# Wind_Tree_connect.net
KiCad netlist of a schematic drawn in EAGLE
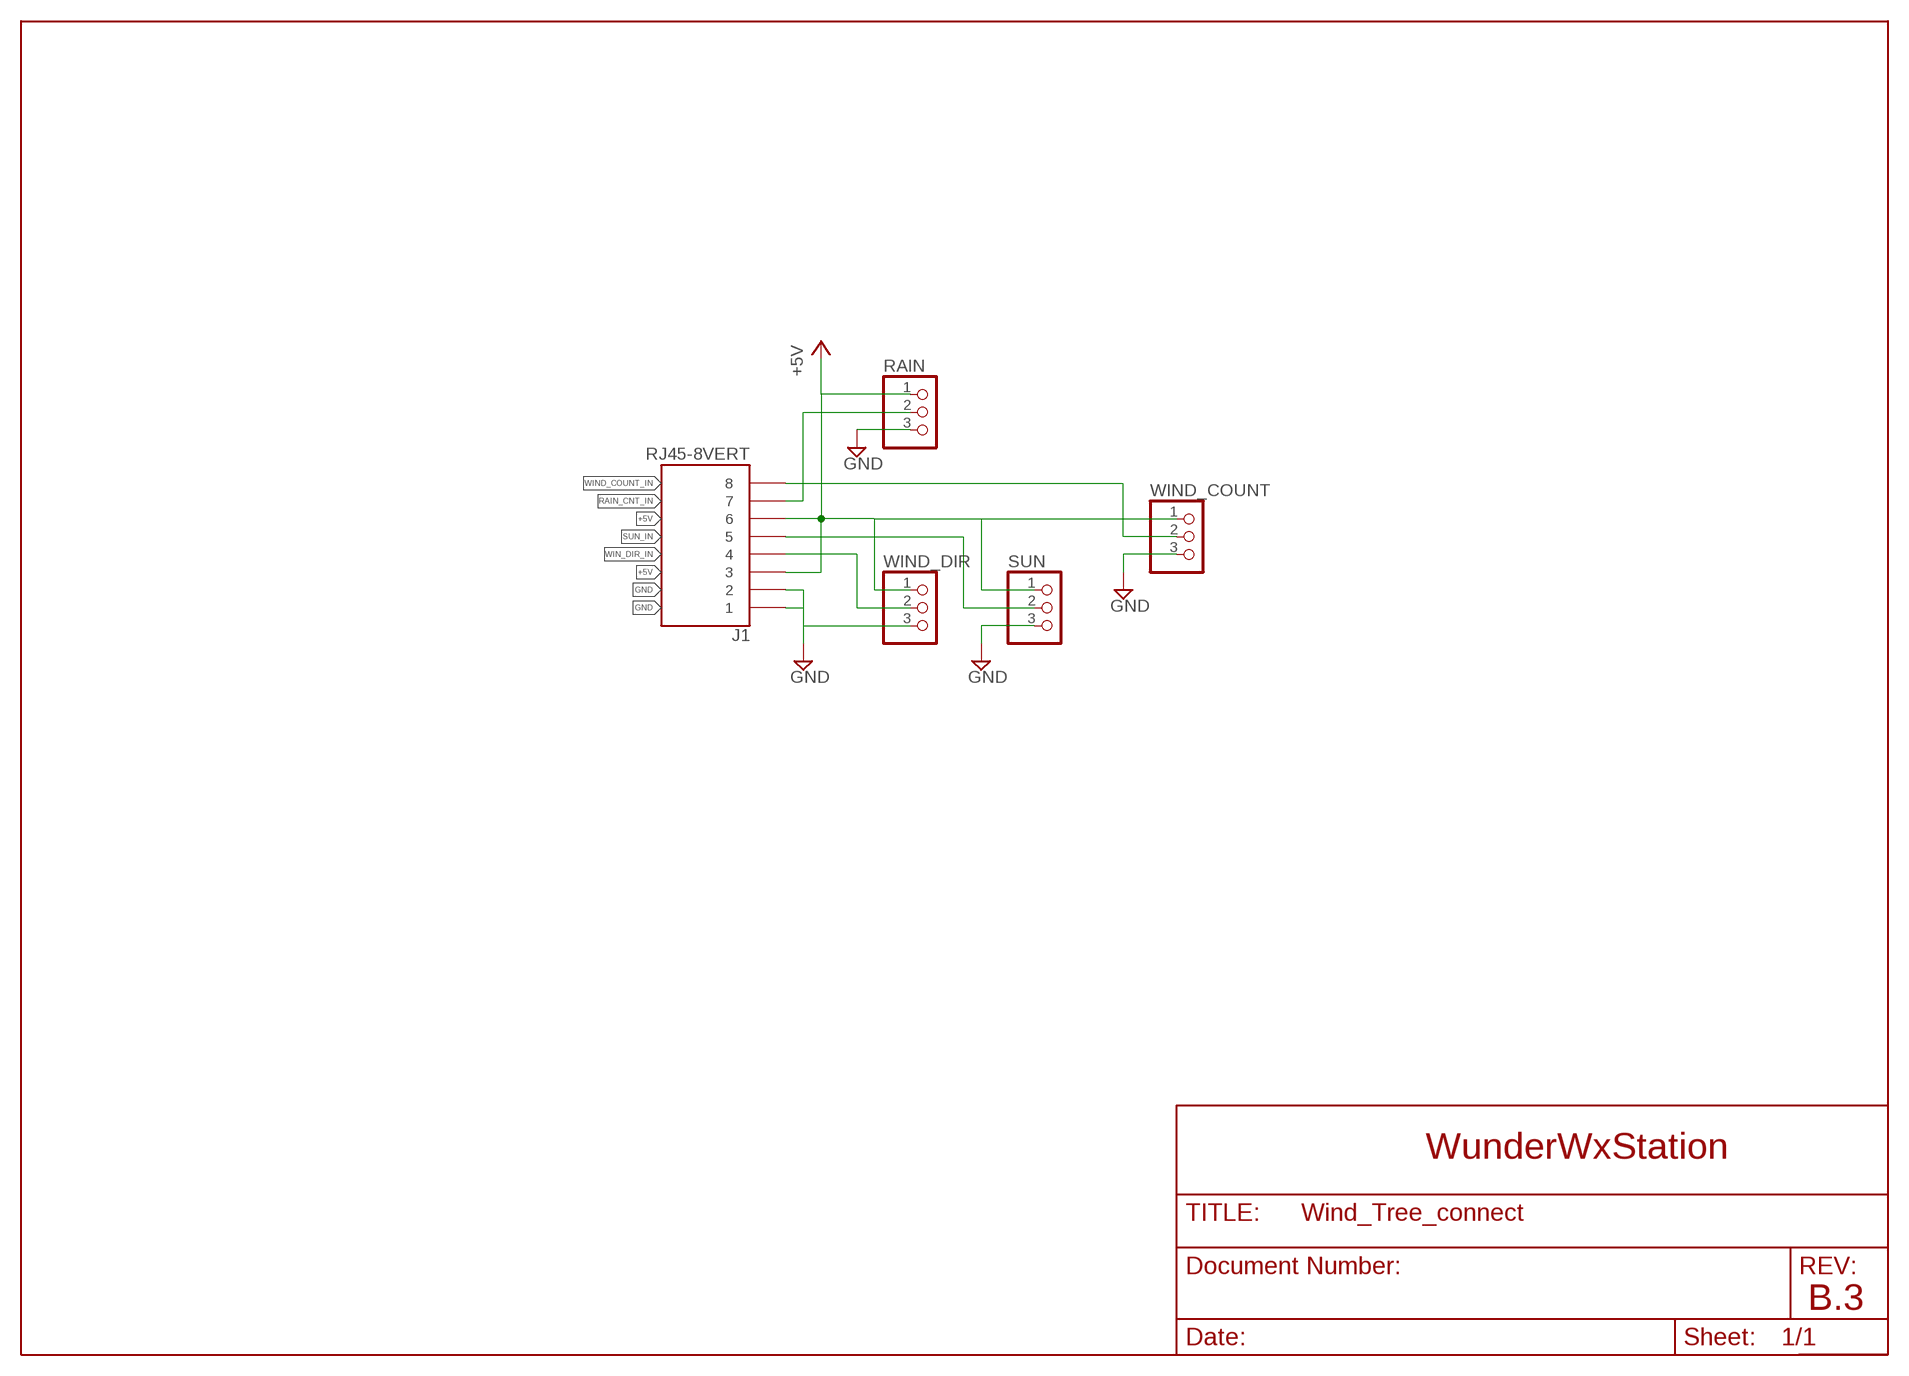
[diagram p0: schematic, sheet 1]

(export (version "E")
  (design (tool "Eeschema 10.0.6"))
  (components
    (comp (ref "J1")
      (value "RJ45-8VERT")
      (footprint "eagle-import:RJ45_VERT")
      (libsource (lib "eagle-import") (part "RJ45-8VERT"))
    )
    (comp (ref "RAIN")
      (value "PINHD-1X3")
      (footprint "eagle-import:1X03")
      (libsource (lib "eagle-import") (part "PINHD-1X3"))
    )
    (comp (ref "SUN")
      (value "PINHD-1X3")
      (footprint "eagle-import:1X03")
      (libsource (lib "eagle-import") (part "PINHD-1X3"))
    )
    (comp (ref "WIND_COUNT")
      (value "PINHD-1X3")
      (footprint "eagle-import:1X03")
      (libsource (lib "eagle-import") (part "PINHD-1X3"))
    )
    (comp (ref "WIND_DIR")
      (value "PINHD-1X3")
      (footprint "eagle-import:1X03")
      (libsource (lib "eagle-import") (part "PINHD-1X3"))
    )
  )
  (nets
    (net (code "1") (name "+5V") (class "Default")
      (node (ref "J1") (pin "P$3") (pinfunction "3_P$3") (pintype "bidirectional"))
      (node (ref "J1") (pin "P$6") (pinfunction "6_P$6") (pintype "bidirectional"))
      (node (ref "RAIN") (pin "1") (pinfunction "1_1") (pintype "passive"))
      (node (ref "SUN") (pin "1") (pinfunction "1_1") (pintype "passive"))
      (node (ref "WIND_COUNT") (pin "1") (pinfunction "1_1") (pintype "passive"))
      (node (ref "WIND_DIR") (pin "1") (pinfunction "1_1") (pintype "passive"))
    )
    (net (code "2") (name "GND") (class "Default")
      (node (ref "J1") (pin "P$1") (pinfunction "1_P$1") (pintype "bidirectional"))
      (node (ref "J1") (pin "P$2") (pinfunction "2_P$2") (pintype "bidirectional"))
      (node (ref "RAIN") (pin "3") (pinfunction "3_3") (pintype "passive"))
      (node (ref "SUN") (pin "3") (pinfunction "3_3") (pintype "passive"))
      (node (ref "WIND_COUNT") (pin "3") (pinfunction "3_3") (pintype "passive"))
      (node (ref "WIND_DIR") (pin "3") (pinfunction "3_3") (pintype "passive"))
    )
    (net (code "3") (name "RAIN_CNT_IN") (class "Default")
      (node (ref "J1") (pin "P$7") (pinfunction "7_P$7") (pintype "bidirectional"))
      (node (ref "RAIN") (pin "2") (pinfunction "2_2") (pintype "passive"))
    )
    (net (code "4") (name "SUN_IN") (class "Default")
      (node (ref "J1") (pin "P$5") (pinfunction "5_P$5") (pintype "bidirectional"))
      (node (ref "SUN") (pin "2") (pinfunction "2_2") (pintype "passive"))
    )
    (net (code "5") (name "WIND_COUNT_IN") (class "Default")
      (node (ref "J1") (pin "P$8") (pinfunction "8_P$8") (pintype "bidirectional"))
      (node (ref "WIND_COUNT") (pin "2") (pinfunction "2_2") (pintype "passive"))
    )
    (net (code "6") (name "WIN_DIR_IN") (class "Default")
      (node (ref "J1") (pin "P$4") (pinfunction "4_P$4") (pintype "bidirectional"))
      (node (ref "WIND_DIR") (pin "2") (pinfunction "2_2") (pintype "passive"))
    )
  )
)
